# Simple_Boost_AAA_to_1V8.net
KiCad netlist of a schematic drawn in EAGLE
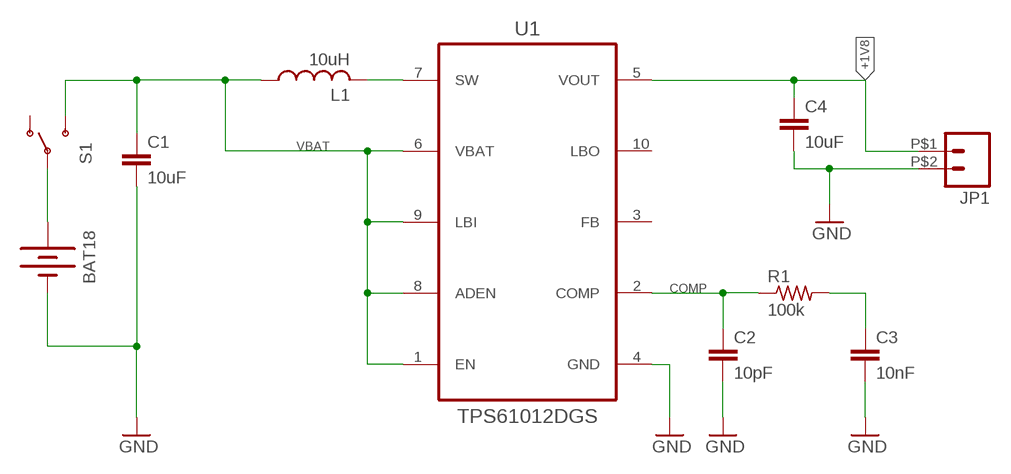
[diagram p0: schematic, sheet 1]

(export (version "E")
  (design (tool "Eeschema 10.0.6"))
  (components
    (comp (ref "BAT18")
      (value "BATTERYAAA")
      (footprint "eagle-import:BATTERY-AAA")
      (libsource (lib "eagle-import") (part "BATTERYAAA"))
    )
    (comp (ref "C1")
      (value "10uF")
      (footprint "eagle-import:C1812")
      (libsource (lib "eagle-import") (part "C-EUC1812"))
    )
    (comp (ref "C2")
      (value "10pF")
      (footprint "eagle-import:C0805")
      (libsource (lib "eagle-import") (part "C-EUC0805"))
    )
    (comp (ref "C3")
      (value "10nF")
      (footprint "eagle-import:C0805")
      (libsource (lib "eagle-import") (part "C-EUC0805"))
    )
    (comp (ref "C4")
      (value "10uF")
      (footprint "eagle-import:C1812")
      (libsource (lib "eagle-import") (part "C-EUC1812"))
    )
    (comp (ref "JP1")
      (value "M02TE-282834-2")
      (footprint "eagle-import:1X02_282834-2")
      (libsource (lib "eagle-import") (part "M02TE-282834-2"))
    )
    (comp (ref "L1")
      (value "10uH")
      (footprint "eagle-import:CDRH6D38")
      (libsource (lib "eagle-import") (part "SUMIDA_POWER_INDUCTOR6"))
    )
    (comp (ref "R1")
      (value "100k")
      (footprint "eagle-import:R0805")
      (libsource (lib "eagle-import") (part "R-US_R0805"))
    )
    (comp (ref "S1")
      (value "SWITCH-SPDTPTH")
      (footprint "eagle-import:SWITCH-SPDT")
      (libsource (lib "eagle-import") (part "SWITCH-SPDTPTH"))
    )
    (comp (ref "U1")
      (value "TPS61012DGS")
      (footprint "eagle-import:SOP50P490X110-10N")
      (fields (field (name "VOLTAGE") "1.8"))
      (libsource (lib "eagle-import") (part "TPS6101DGS2"))
    )
  )
  (nets
    (net (code "1") (name "+1V8") (class "Default")
      (node (ref "C4") (pin "1") (pinfunction "1_1") (pintype "passive"))
      (node (ref "JP1") (pin "P$1") (pinfunction "1_P$1") (pintype "passive"))
      (node (ref "U1") (pin "5") (pinfunction "VOUT_5") (pintype "output"))
    )
    (net (code "2") (name "/COMP") (class "Default")
      (node (ref "C2") (pin "1") (pinfunction "1_1") (pintype "passive"))
      (node (ref "R1") (pin "1") (pinfunction "1_1") (pintype "passive"))
      (node (ref "U1") (pin "2") (pinfunction "COMP_2") (pintype "input"))
    )
    (net (code "3") (name "/VBAT") (class "Default")
      (node (ref "C1") (pin "1") (pinfunction "1_1") (pintype "passive"))
      (node (ref "L1") (pin "P$1") (pinfunction "1_P$1") (pintype "passive"))
      (node (ref "S1") (pin "3") (pinfunction "S_3") (pintype "passive"))
      (node (ref "U1") (pin "1") (pinfunction "EN_1") (pintype "input"))
      (node (ref "U1") (pin "6") (pinfunction "VBAT_6") (pintype "power_in"))
      (node (ref "U1") (pin "8") (pinfunction "ADEN_8") (pintype "input"))
      (node (ref "U1") (pin "9") (pinfunction "LBI_9") (pintype "input"))
    )
    (net (code "4") (name "GND") (class "Default")
      (node (ref "BAT18") (pin "GND@1") (pinfunction "-_GND@1") (pintype "power_in"))
      (node (ref "BAT18") (pin "GND@2") (pinfunction "-_GND@2") (pintype "power_in"))
      (node (ref "C1") (pin "2") (pinfunction "2_2") (pintype "passive"))
      (node (ref "C2") (pin "2") (pinfunction "2_2") (pintype "passive"))
      (node (ref "C3") (pin "2") (pinfunction "2_2") (pintype "passive"))
      (node (ref "C4") (pin "2") (pinfunction "2_2") (pintype "passive"))
      (node (ref "JP1") (pin "P$2") (pinfunction "2_P$2") (pintype "passive"))
      (node (ref "U1") (pin "4") (pinfunction "GND_4") (pintype "passive"))
    )
    (net (code "5") (name "Net-(C3-Pad1)") (class "Default")
      (node (ref "C3") (pin "1") (pinfunction "1_1") (pintype "passive"))
      (node (ref "R1") (pin "2") (pinfunction "2_2") (pintype "passive"))
    )
    (net (code "6") (name "Net-(L1-2)") (class "Default")
      (node (ref "L1") (pin "P$2") (pinfunction "2_P$2") (pintype "passive"))
      (node (ref "U1") (pin "7") (pinfunction "SW_7") (pintype "input"))
    )
    (net (code "7") (name "Net-(S1-P)") (class "Default")
      (node (ref "BAT18") (pin "PWR@1") (pinfunction "+_PWR@1") (pintype "power_in"))
      (node (ref "BAT18") (pin "PWR@2") (pinfunction "+_PWR@2") (pintype "power_in"))
      (node (ref "S1") (pin "2") (pinfunction "P_2") (pintype "passive"))
    )
    (net (code "8") (name "unconnected-(S1-O-Pad1)") (class "Default")
      (node (ref "S1") (pin "1") (pinfunction "O_1") (pintype "passive"))
    )
    (net (code "9") (name "unconnected-(U1-FB-Pad3)") (class "Default")
      (node (ref "U1") (pin "3") (pinfunction "FB_3") (pintype "input"))
    )
    (net (code "10") (name "unconnected-(U1-LBO-Pad10)") (class "Default")
      (node (ref "U1") (pin "10") (pinfunction "LBO_10") (pintype "output"))
    )
  )
)
